# 8CH_RELAY_CARD.net
KiCad netlist of a schematic drawn in Altium Designer
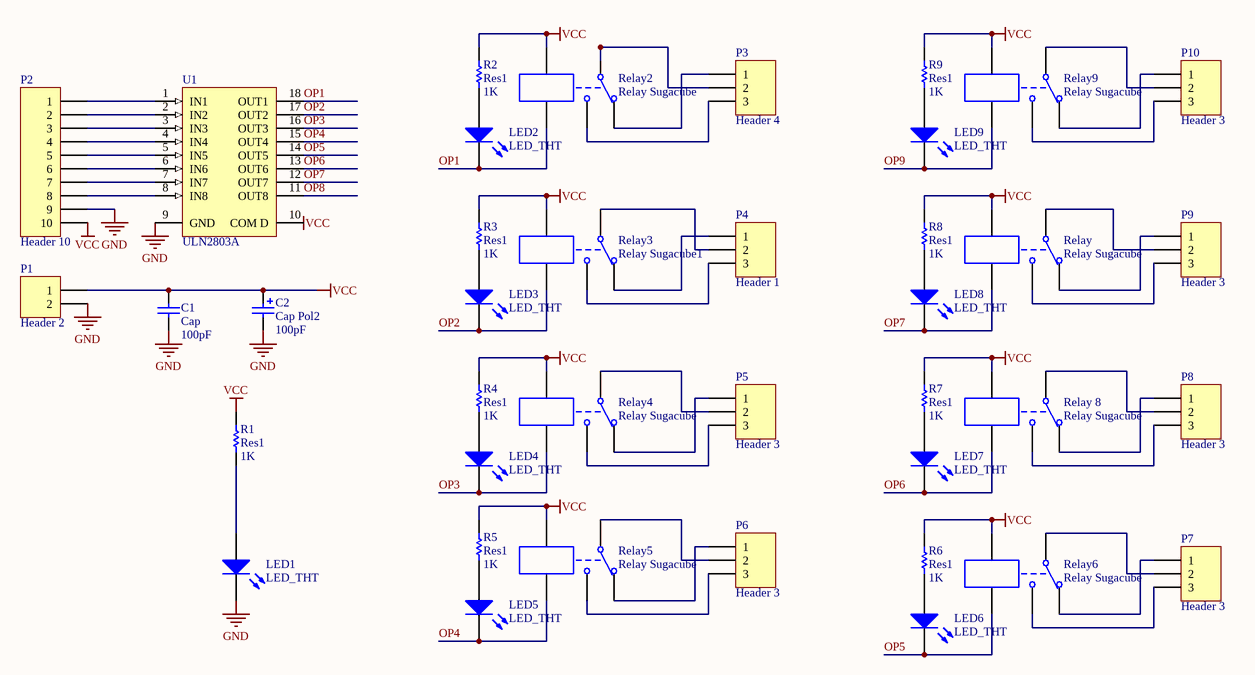
[diagram p0: 8CH_RELAY_CARD.SchDoc]

(export (version "E")
  (design (tool "Eeschema 10.0.6"))
  (components
    (comp (ref "C1")
      (value "Cap")
      (footprint "RAD-0.3")
      (description "Capacitor")
      (fields (field (name "ALTIUM_VALUE") "100pF") (field (name "PUBLISHER") "Altium Limited"))
      (libsource (lib "Miscellaneous Devices") (part "Cap"))
    )
    (comp (ref "C2")
      (value "Cap Pol2")
      (footprint "POLAR0.8")
      (description "Polarized Capacitor (Axial)")
      (fields (field (name "ALTIUM_VALUE") "100pF") (field (name "PUBLISHER") "Altium Limited"))
      (libsource (lib "Miscellaneous Devices") (part "Cap Pol2"))
    )
    (comp (ref "LED1")
      (value "LED_THT")
      (footprint "3MM_LED")
      (libsource (lib "Library_Basic_Discrete") (part "LED_THT"))
    )
    (comp (ref "LED2")
      (value "LED_THT")
      (footprint "3MM_LED")
      (libsource (lib "Library_Basic_Discrete") (part "LED_THT"))
    )
    (comp (ref "LED3")
      (value "LED_THT")
      (footprint "3MM_LED")
      (libsource (lib "Library_Basic_Discrete") (part "LED_THT"))
    )
    (comp (ref "LED4")
      (value "LED_THT")
      (footprint "3MM_LED")
      (libsource (lib "Library_Basic_Discrete") (part "LED_THT"))
    )
    (comp (ref "LED5")
      (value "LED_THT")
      (footprint "3MM_LED")
      (libsource (lib "Library_Basic_Discrete") (part "LED_THT"))
    )
    (comp (ref "LED6")
      (value "LED_THT")
      (footprint "3MM_LED")
      (libsource (lib "Library_Basic_Discrete") (part "LED_THT"))
    )
    (comp (ref "LED7")
      (value "LED_THT")
      (footprint "3MM_LED")
      (libsource (lib "Library_Basic_Discrete") (part "LED_THT"))
    )
    (comp (ref "LED8")
      (value "LED_THT")
      (footprint "3MM_LED")
      (libsource (lib "Library_Basic_Discrete") (part "LED_THT"))
    )
    (comp (ref "LED9")
      (value "LED_THT")
      (footprint "3MM_LED")
      (libsource (lib "Library_Basic_Discrete") (part "LED_THT"))
    )
    (comp (ref "P1")
      (value "Header 2")
      (footprint "HDR1X2")
      (description "Header, 2-Pin")
      (fields (field (name "PUBLISHER") "Altium Limited"))
      (libsource (lib "Miscellaneous Connectors") (part "Header 2"))
    )
    (comp (ref "P2")
      (value "Header 10")
      (footprint "HDR1X10")
      (description "Header, 10-Pin")
      (fields (field (name "PUBLISHER") "Altium Limited"))
      (libsource (lib "Miscellaneous Connectors") (part "Header 10"))
    )
    (comp (ref "P3")
      (value "Header 4")
      (footprint "HDR1X3")
      (description "Header, 3-Pin")
      (fields (field (name "PUBLISHER") "Altium Limited"))
      (libsource (lib "Miscellaneous Connectors") (part "Header 3"))
    )
    (comp (ref "P4")
      (value "Header 1")
      (footprint "HDR1X3")
      (description "Header, 3-Pin")
      (fields (field (name "PUBLISHER") "Altium Limited"))
      (libsource (lib "Miscellaneous Connectors") (part "Header 3"))
    )
    (comp (ref "P5")
      (value "Header 3")
      (footprint "HDR1X3")
      (description "Header, 3-Pin")
      (fields (field (name "PUBLISHER") "Altium Limited"))
      (libsource (lib "Miscellaneous Connectors") (part "Header 3"))
    )
    (comp (ref "P6")
      (value "Header 3")
      (footprint "HDR1X3")
      (description "Header, 3-Pin")
      (fields (field (name "PUBLISHER") "Altium Limited"))
      (libsource (lib "Miscellaneous Connectors") (part "Header 3"))
    )
    (comp (ref "P7")
      (value "Header 3")
      (footprint "HDR1X3")
      (description "Header, 3-Pin")
      (fields (field (name "PUBLISHER") "Altium Limited"))
      (libsource (lib "Miscellaneous Connectors") (part "Header 3"))
    )
    (comp (ref "P8")
      (value "Header 3")
      (footprint "HDR1X3")
      (description "Header, 3-Pin")
      (fields (field (name "PUBLISHER") "Altium Limited"))
      (libsource (lib "Miscellaneous Connectors") (part "Header 3"))
    )
    (comp (ref "P9")
      (value "Header 3")
      (footprint "HDR1X3")
      (description "Header, 3-Pin")
      (fields (field (name "PUBLISHER") "Altium Limited"))
      (libsource (lib "Miscellaneous Connectors") (part "Header 3"))
    )
    (comp (ref "P10")
      (value "Header 3")
      (footprint "HDR1X3")
      (description "Header, 3-Pin")
      (fields (field (name "PUBLISHER") "Altium Limited"))
      (libsource (lib "Miscellaneous Connectors") (part "Header 3"))
    )
    (comp (ref "R1")
      (value "Res1")
      (footprint "AXIAL-0.3")
      (description "Resistor")
      (fields (field (name "ALTIUM_VALUE") "1K") (field (name "PUBLISHER") "Altium Limited"))
      (libsource (lib "Miscellaneous Devices") (part "Res1"))
    )
    (comp (ref "R2")
      (value "Res1")
      (footprint "AXIAL-0.3")
      (description "Resistor")
      (fields (field (name "ALTIUM_VALUE") "1K") (field (name "PUBLISHER") "Altium Limited"))
      (libsource (lib "Miscellaneous Devices") (part "Res1"))
    )
    (comp (ref "R3")
      (value "Res1")
      (footprint "AXIAL-0.3")
      (description "Resistor")
      (fields (field (name "ALTIUM_VALUE") "1K") (field (name "PUBLISHER") "Altium Limited"))
      (libsource (lib "Miscellaneous Devices") (part "Res1"))
    )
    (comp (ref "R4")
      (value "Res1")
      (footprint "AXIAL-0.3")
      (description "Resistor")
      (fields (field (name "ALTIUM_VALUE") "1K") (field (name "PUBLISHER") "Altium Limited"))
      (libsource (lib "Miscellaneous Devices") (part "Res1"))
    )
    (comp (ref "R5")
      (value "Res1")
      (footprint "AXIAL-0.3")
      (description "Resistor")
      (fields (field (name "ALTIUM_VALUE") "1K") (field (name "PUBLISHER") "Altium Limited"))
      (libsource (lib "Miscellaneous Devices") (part "Res1"))
    )
    (comp (ref "R6")
      (value "Res1")
      (footprint "AXIAL-0.3")
      (description "Resistor")
      (fields (field (name "ALTIUM_VALUE") "1K") (field (name "PUBLISHER") "Altium Limited"))
      (libsource (lib "Miscellaneous Devices") (part "Res1"))
    )
    (comp (ref "R7")
      (value "Res1")
      (footprint "AXIAL-0.3")
      (description "Resistor")
      (fields (field (name "ALTIUM_VALUE") "1K") (field (name "PUBLISHER") "Altium Limited"))
      (libsource (lib "Miscellaneous Devices") (part "Res1"))
    )
    (comp (ref "R8")
      (value "Res1")
      (footprint "AXIAL-0.3")
      (description "Resistor")
      (fields (field (name "ALTIUM_VALUE") "1K") (field (name "PUBLISHER") "Altium Limited"))
      (libsource (lib "Miscellaneous Devices") (part "Res1"))
    )
    (comp (ref "R9")
      (value "Res1")
      (footprint "AXIAL-0.3")
      (description "Resistor")
      (fields (field (name "ALTIUM_VALUE") "1K") (field (name "PUBLISHER") "Altium Limited"))
      (libsource (lib "Miscellaneous Devices") (part "Res1"))
    )
    (comp (ref "Relay")
      (value "Relay Sugacube")
      (footprint "Relay_Sugarcube")
      (libsource (lib "Library_Basic_Discrete") (part "Relay Sugacube"))
    )
    (comp (ref "Relay 8")
      (value "Relay Sugacube")
      (footprint "Relay_Sugarcube")
      (libsource (lib "Library_Basic_Discrete") (part "Relay Sugacube"))
    )
    (comp (ref "Relay2")
      (value "Relay Sugacube")
      (footprint "Relay_Sugarcube")
      (libsource (lib "Library_Basic_Discrete") (part "Relay Sugacube"))
    )
    (comp (ref "Relay3")
      (value "Relay Sugacube1")
      (footprint "Relay_Sugarcube")
      (description "Relay Sugacube")
      (libsource (lib "Library_Basic_Discrete") (part "Relay Sugacube"))
    )
    (comp (ref "Relay4")
      (value "Relay Sugacube")
      (footprint "Relay_Sugarcube")
      (libsource (lib "Library_Basic_Discrete") (part "Relay Sugacube"))
    )
    (comp (ref "Relay5")
      (value "Relay Sugacube")
      (footprint "Relay_Sugarcube")
      (libsource (lib "Library_Basic_Discrete") (part "Relay Sugacube"))
    )
    (comp (ref "Relay6")
      (value "Relay Sugacube")
      (footprint "Relay_Sugarcube")
      (libsource (lib "Library_Basic_Discrete") (part "Relay Sugacube"))
    )
    (comp (ref "Relay9")
      (value "Relay Sugacube")
      (footprint "Relay_Sugarcube")
      (libsource (lib "Library_Basic_Discrete") (part "Relay Sugacube"))
    )
    (comp (ref "U1")
      (value "ULN2803A")
      (footprint "A18")
      (description "High-Voltage, High-Current Darlington Array")
      (fields (field (name "PUBLISHER") "Altium Limited"))
      (libsource (lib "Allegro Interface Darlington Driver") (part "ULN2803A"))
    )
  )
  (nets
    (net (code "1") (name "/OP1") (class "Default")
      (node (ref "LED2") (pin "2") (pinfunction "K_2") (pintype "passive"))
      (node (ref "Relay2") (pin "5") (pinfunction "5_5") (pintype "passive"))
      (node (ref "U1") (pin "18") (pinfunction "OUT1_18") (pintype "open_collector"))
    )
    (net (code "2") (name "/OP2") (class "Default")
      (node (ref "LED3") (pin "2") (pinfunction "K_2") (pintype "passive"))
      (node (ref "Relay3") (pin "5") (pinfunction "5_5") (pintype "passive"))
      (node (ref "U1") (pin "17") (pinfunction "OUT2_17") (pintype "open_collector"))
    )
    (net (code "3") (name "/OP3") (class "Default")
      (node (ref "LED4") (pin "2") (pinfunction "K_2") (pintype "passive"))
      (node (ref "Relay4") (pin "5") (pinfunction "5_5") (pintype "passive"))
      (node (ref "U1") (pin "16") (pinfunction "OUT3_16") (pintype "open_collector"))
    )
    (net (code "4") (name "/OP4") (class "Default")
      (node (ref "LED5") (pin "2") (pinfunction "K_2") (pintype "passive"))
      (node (ref "Relay5") (pin "5") (pinfunction "5_5") (pintype "passive"))
      (node (ref "U1") (pin "15") (pinfunction "OUT4_15") (pintype "open_collector"))
    )
    (net (code "5") (name "/OP5") (class "Default")
      (node (ref "LED6") (pin "2") (pinfunction "K_2") (pintype "passive"))
      (node (ref "Relay6") (pin "5") (pinfunction "5_5") (pintype "passive"))
      (node (ref "U1") (pin "14") (pinfunction "OUT5_14") (pintype "open_collector"))
    )
    (net (code "6") (name "/OP6") (class "Default")
      (node (ref "LED7") (pin "2") (pinfunction "K_2") (pintype "passive"))
      (node (ref "Relay 8") (pin "5") (pinfunction "5_5") (pintype "passive"))
      (node (ref "U1") (pin "13") (pinfunction "OUT6_13") (pintype "open_collector"))
    )
    (net (code "7") (name "/OP7") (class "Default")
      (node (ref "LED8") (pin "2") (pinfunction "K_2") (pintype "passive"))
      (node (ref "Relay") (pin "5") (pinfunction "5_5") (pintype "passive"))
      (node (ref "U1") (pin "12") (pinfunction "OUT7_12") (pintype "open_collector"))
    )
    (net (code "8") (name "/OP8") (class "Default")
      (node (ref "U1") (pin "11") (pinfunction "OUT8_11") (pintype "open_collector"))
    )
    (net (code "9") (name "/OP9") (class "Default")
      (node (ref "LED9") (pin "2") (pinfunction "K_2") (pintype "passive"))
      (node (ref "Relay9") (pin "5") (pinfunction "5_5") (pintype "passive"))
    )
    (net (code "10") (name "GND") (class "Default")
      (node (ref "C1") (pin "1") (pinfunction "1_1") (pintype "passive"))
      (node (ref "C2") (pin "2") (pinfunction "2_2") (pintype "passive"))
      (node (ref "LED1") (pin "2") (pinfunction "K_2") (pintype "passive"))
      (node (ref "P1") (pin "2") (pinfunction "2_2") (pintype "passive"))
      (node (ref "P2") (pin "9") (pinfunction "9_9") (pintype "passive"))
      (node (ref "U1") (pin "9") (pinfunction "GND_9") (pintype "power_in"))
    )
    (net (code "11") (name "Net-(LED1-A)") (class "Default")
      (node (ref "LED1") (pin "1") (pinfunction "A_1") (pintype "passive"))
      (node (ref "R1") (pin "1") (pinfunction "1_1") (pintype "passive"))
    )
    (net (code "12") (name "Net-(LED2-A)") (class "Default")
      (node (ref "LED2") (pin "1") (pinfunction "A_1") (pintype "passive"))
      (node (ref "R2") (pin "1") (pinfunction "1_1") (pintype "passive"))
    )
    (net (code "13") (name "Net-(LED3-A)") (class "Default")
      (node (ref "LED3") (pin "1") (pinfunction "A_1") (pintype "passive"))
      (node (ref "R3") (pin "1") (pinfunction "1_1") (pintype "passive"))
    )
    (net (code "14") (name "Net-(LED4-A)") (class "Default")
      (node (ref "LED4") (pin "1") (pinfunction "A_1") (pintype "passive"))
      (node (ref "R4") (pin "1") (pinfunction "1_1") (pintype "passive"))
    )
    (net (code "15") (name "Net-(LED5-A)") (class "Default")
      (node (ref "LED5") (pin "1") (pinfunction "A_1") (pintype "passive"))
      (node (ref "R5") (pin "1") (pinfunction "1_1") (pintype "passive"))
    )
    (net (code "16") (name "Net-(LED6-A)") (class "Default")
      (node (ref "LED6") (pin "1") (pinfunction "A_1") (pintype "passive"))
      (node (ref "R6") (pin "1") (pinfunction "1_1") (pintype "passive"))
    )
    (net (code "17") (name "Net-(LED7-A)") (class "Default")
      (node (ref "LED7") (pin "1") (pinfunction "A_1") (pintype "passive"))
      (node (ref "R7") (pin "1") (pinfunction "1_1") (pintype "passive"))
    )
    (net (code "18") (name "Net-(LED8-A)") (class "Default")
      (node (ref "LED8") (pin "1") (pinfunction "A_1") (pintype "passive"))
      (node (ref "R8") (pin "1") (pinfunction "1_1") (pintype "passive"))
    )
    (net (code "19") (name "Net-(LED9-A)") (class "Default")
      (node (ref "LED9") (pin "1") (pinfunction "A_1") (pintype "passive"))
      (node (ref "R9") (pin "1") (pinfunction "1_1") (pintype "passive"))
    )
    (net (code "20") (name "Net-(P3-Pad1)") (class "Default")
      (node (ref "P3") (pin "1") (pinfunction "1_1") (pintype "passive"))
      (node (ref "Relay2") (pin "2") (pinfunction "2_2") (pintype "passive"))
    )
    (net (code "21") (name "Net-(P3-Pad2)") (class "Default")
      (node (ref "P3") (pin "2") (pinfunction "2_2") (pintype "passive"))
      (node (ref "Relay2") (pin "1") (pinfunction "1_1") (pintype "passive"))
    )
    (net (code "22") (name "Net-(P3-Pad3)") (class "Default")
      (node (ref "P3") (pin "3") (pinfunction "3_3") (pintype "passive"))
      (node (ref "Relay2") (pin "3") (pinfunction "3_3") (pintype "passive"))
    )
    (net (code "23") (name "Net-(P4-Pad1)") (class "Default")
      (node (ref "P4") (pin "1") (pinfunction "1_1") (pintype "passive"))
      (node (ref "Relay3") (pin "2") (pinfunction "2_2") (pintype "passive"))
    )
    (net (code "24") (name "Net-(P4-Pad2)") (class "Default")
      (node (ref "P4") (pin "2") (pinfunction "2_2") (pintype "passive"))
      (node (ref "Relay3") (pin "1") (pinfunction "1_1") (pintype "passive"))
    )
    (net (code "25") (name "Net-(P4-Pad3)") (class "Default")
      (node (ref "P4") (pin "3") (pinfunction "3_3") (pintype "passive"))
      (node (ref "Relay3") (pin "3") (pinfunction "3_3") (pintype "passive"))
    )
    (net (code "26") (name "Net-(P5-Pad1)") (class "Default")
      (node (ref "P5") (pin "1") (pinfunction "1_1") (pintype "passive"))
      (node (ref "Relay4") (pin "2") (pinfunction "2_2") (pintype "passive"))
    )
    (net (code "27") (name "Net-(P5-Pad2)") (class "Default")
      (node (ref "P5") (pin "2") (pinfunction "2_2") (pintype "passive"))
      (node (ref "Relay4") (pin "1") (pinfunction "1_1") (pintype "passive"))
    )
    (net (code "28") (name "Net-(P5-Pad3)") (class "Default")
      (node (ref "P5") (pin "3") (pinfunction "3_3") (pintype "passive"))
      (node (ref "Relay4") (pin "3") (pinfunction "3_3") (pintype "passive"))
    )
    (net (code "29") (name "Net-(P6-Pad1)") (class "Default")
      (node (ref "P6") (pin "1") (pinfunction "1_1") (pintype "passive"))
      (node (ref "Relay5") (pin "2") (pinfunction "2_2") (pintype "passive"))
    )
    (net (code "30") (name "Net-(P6-Pad2)") (class "Default")
      (node (ref "P6") (pin "2") (pinfunction "2_2") (pintype "passive"))
      (node (ref "Relay5") (pin "1") (pinfunction "1_1") (pintype "passive"))
    )
    (net (code "31") (name "Net-(P6-Pad3)") (class "Default")
      (node (ref "P6") (pin "3") (pinfunction "3_3") (pintype "passive"))
      (node (ref "Relay5") (pin "3") (pinfunction "3_3") (pintype "passive"))
    )
    (net (code "32") (name "Net-(P7-Pad1)") (class "Default")
      (node (ref "P7") (pin "1") (pinfunction "1_1") (pintype "passive"))
      (node (ref "Relay6") (pin "2") (pinfunction "2_2") (pintype "passive"))
    )
    (net (code "33") (name "Net-(P7-Pad2)") (class "Default")
      (node (ref "P7") (pin "2") (pinfunction "2_2") (pintype "passive"))
      (node (ref "Relay6") (pin "1") (pinfunction "1_1") (pintype "passive"))
    )
    (net (code "34") (name "Net-(P7-Pad3)") (class "Default")
      (node (ref "P7") (pin "3") (pinfunction "3_3") (pintype "passive"))
      (node (ref "Relay6") (pin "3") (pinfunction "3_3") (pintype "passive"))
    )
    (net (code "35") (name "Net-(P8-Pad1)") (class "Default")
      (node (ref "P8") (pin "1") (pinfunction "1_1") (pintype "passive"))
      (node (ref "Relay 8") (pin "2") (pinfunction "2_2") (pintype "passive"))
    )
    (net (code "36") (name "Net-(P8-Pad2)") (class "Default")
      (node (ref "P8") (pin "2") (pinfunction "2_2") (pintype "passive"))
      (node (ref "Relay 8") (pin "1") (pinfunction "1_1") (pintype "passive"))
    )
    (net (code "37") (name "Net-(P8-Pad3)") (class "Default")
      (node (ref "P8") (pin "3") (pinfunction "3_3") (pintype "passive"))
      (node (ref "Relay 8") (pin "3") (pinfunction "3_3") (pintype "passive"))
    )
    (net (code "38") (name "Net-(P9-Pad1)") (class "Default")
      (node (ref "P9") (pin "1") (pinfunction "1_1") (pintype "passive"))
      (node (ref "Relay") (pin "2") (pinfunction "2_2") (pintype "passive"))
    )
    (net (code "39") (name "Net-(P9-Pad2)") (class "Default")
      (node (ref "P9") (pin "2") (pinfunction "2_2") (pintype "passive"))
      (node (ref "Relay") (pin "1") (pinfunction "1_1") (pintype "passive"))
    )
    (net (code "40") (name "Net-(P9-Pad3)") (class "Default")
      (node (ref "P9") (pin "3") (pinfunction "3_3") (pintype "passive"))
      (node (ref "Relay") (pin "3") (pinfunction "3_3") (pintype "passive"))
    )
    (net (code "41") (name "Net-(P10-Pad1)") (class "Default")
      (node (ref "P10") (pin "1") (pinfunction "1_1") (pintype "passive"))
      (node (ref "Relay9") (pin "2") (pinfunction "2_2") (pintype "passive"))
    )
    (net (code "42") (name "Net-(P10-Pad2)") (class "Default")
      (node (ref "P10") (pin "2") (pinfunction "2_2") (pintype "passive"))
      (node (ref "Relay9") (pin "1") (pinfunction "1_1") (pintype "passive"))
    )
    (net (code "43") (name "Net-(P10-Pad3)") (class "Default")
      (node (ref "P10") (pin "3") (pinfunction "3_3") (pintype "passive"))
      (node (ref "Relay9") (pin "3") (pinfunction "3_3") (pintype "passive"))
    )
    (net (code "44") (name "Net-(U1-IN1)") (class "Default")
      (node (ref "P2") (pin "1") (pinfunction "1_1") (pintype "passive"))
      (node (ref "U1") (pin "1") (pinfunction "IN1_1") (pintype "input"))
    )
    (net (code "45") (name "Net-(U1-IN2)") (class "Default")
      (node (ref "P2") (pin "2") (pinfunction "2_2") (pintype "passive"))
      (node (ref "U1") (pin "2") (pinfunction "IN2_2") (pintype "input"))
    )
    (net (code "46") (name "Net-(U1-IN3)") (class "Default")
      (node (ref "P2") (pin "3") (pinfunction "3_3") (pintype "passive"))
      (node (ref "U1") (pin "3") (pinfunction "IN3_3") (pintype "input"))
    )
    (net (code "47") (name "Net-(U1-IN4)") (class "Default")
      (node (ref "P2") (pin "4") (pinfunction "4_4") (pintype "passive"))
      (node (ref "U1") (pin "4") (pinfunction "IN4_4") (pintype "input"))
    )
    (net (code "48") (name "Net-(U1-IN5)") (class "Default")
      (node (ref "P2") (pin "5") (pinfunction "5_5") (pintype "passive"))
      (node (ref "U1") (pin "5") (pinfunction "IN5_5") (pintype "input"))
    )
    (net (code "49") (name "Net-(U1-IN6)") (class "Default")
      (node (ref "P2") (pin "6") (pinfunction "6_6") (pintype "passive"))
      (node (ref "U1") (pin "6") (pinfunction "IN6_6") (pintype "input"))
    )
    (net (code "50") (name "Net-(U1-IN7)") (class "Default")
      (node (ref "P2") (pin "7") (pinfunction "7_7") (pintype "passive"))
      (node (ref "U1") (pin "7") (pinfunction "IN7_7") (pintype "input"))
    )
    (net (code "51") (name "Net-(U1-IN8)") (class "Default")
      (node (ref "P2") (pin "8") (pinfunction "8_8") (pintype "passive"))
      (node (ref "U1") (pin "8") (pinfunction "IN8_8") (pintype "input"))
    )
    (net (code "52") (name "VCC") (class "Default")
      (node (ref "C1") (pin "2") (pinfunction "2_2") (pintype "passive"))
      (node (ref "C2") (pin "1") (pinfunction "1_1") (pintype "passive"))
      (node (ref "P1") (pin "1") (pinfunction "1_1") (pintype "passive"))
      (node (ref "P2") (pin "10") (pinfunction "10_10") (pintype "passive"))
      (node (ref "R1") (pin "2") (pinfunction "2_2") (pintype "passive"))
      (node (ref "R2") (pin "2") (pinfunction "2_2") (pintype "passive"))
      (node (ref "R3") (pin "2") (pinfunction "2_2") (pintype "passive"))
      (node (ref "R4") (pin "2") (pinfunction "2_2") (pintype "passive"))
      (node (ref "R5") (pin "2") (pinfunction "2_2") (pintype "passive"))
      (node (ref "R6") (pin "2") (pinfunction "2_2") (pintype "passive"))
      (node (ref "R7") (pin "2") (pinfunction "2_2") (pintype "passive"))
      (node (ref "R8") (pin "2") (pinfunction "2_2") (pintype "passive"))
      (node (ref "R9") (pin "2") (pinfunction "2_2") (pintype "passive"))
      (node (ref "Relay") (pin "4") (pinfunction "4_4") (pintype "passive"))
      (node (ref "Relay 8") (pin "4") (pinfunction "4_4") (pintype "passive"))
      (node (ref "Relay2") (pin "4") (pinfunction "4_4") (pintype "passive"))
      (node (ref "Relay3") (pin "4") (pinfunction "4_4") (pintype "passive"))
      (node (ref "Relay4") (pin "4") (pinfunction "4_4") (pintype "passive"))
      (node (ref "Relay5") (pin "4") (pinfunction "4_4") (pintype "passive"))
      (node (ref "Relay6") (pin "4") (pinfunction "4_4") (pintype "passive"))
      (node (ref "Relay9") (pin "4") (pinfunction "4_4") (pintype "passive"))
    )
    (net (code "53") (name "unconnected-(U1-COM_D-Pad10)") (class "Default")
      (node (ref "U1") (pin "10") (pinfunction "COM_D_10") (pintype "passive"))
    )
  )
)
